# Ethernet.net
KiCad netlist of a schematic drawn in Altium Designer
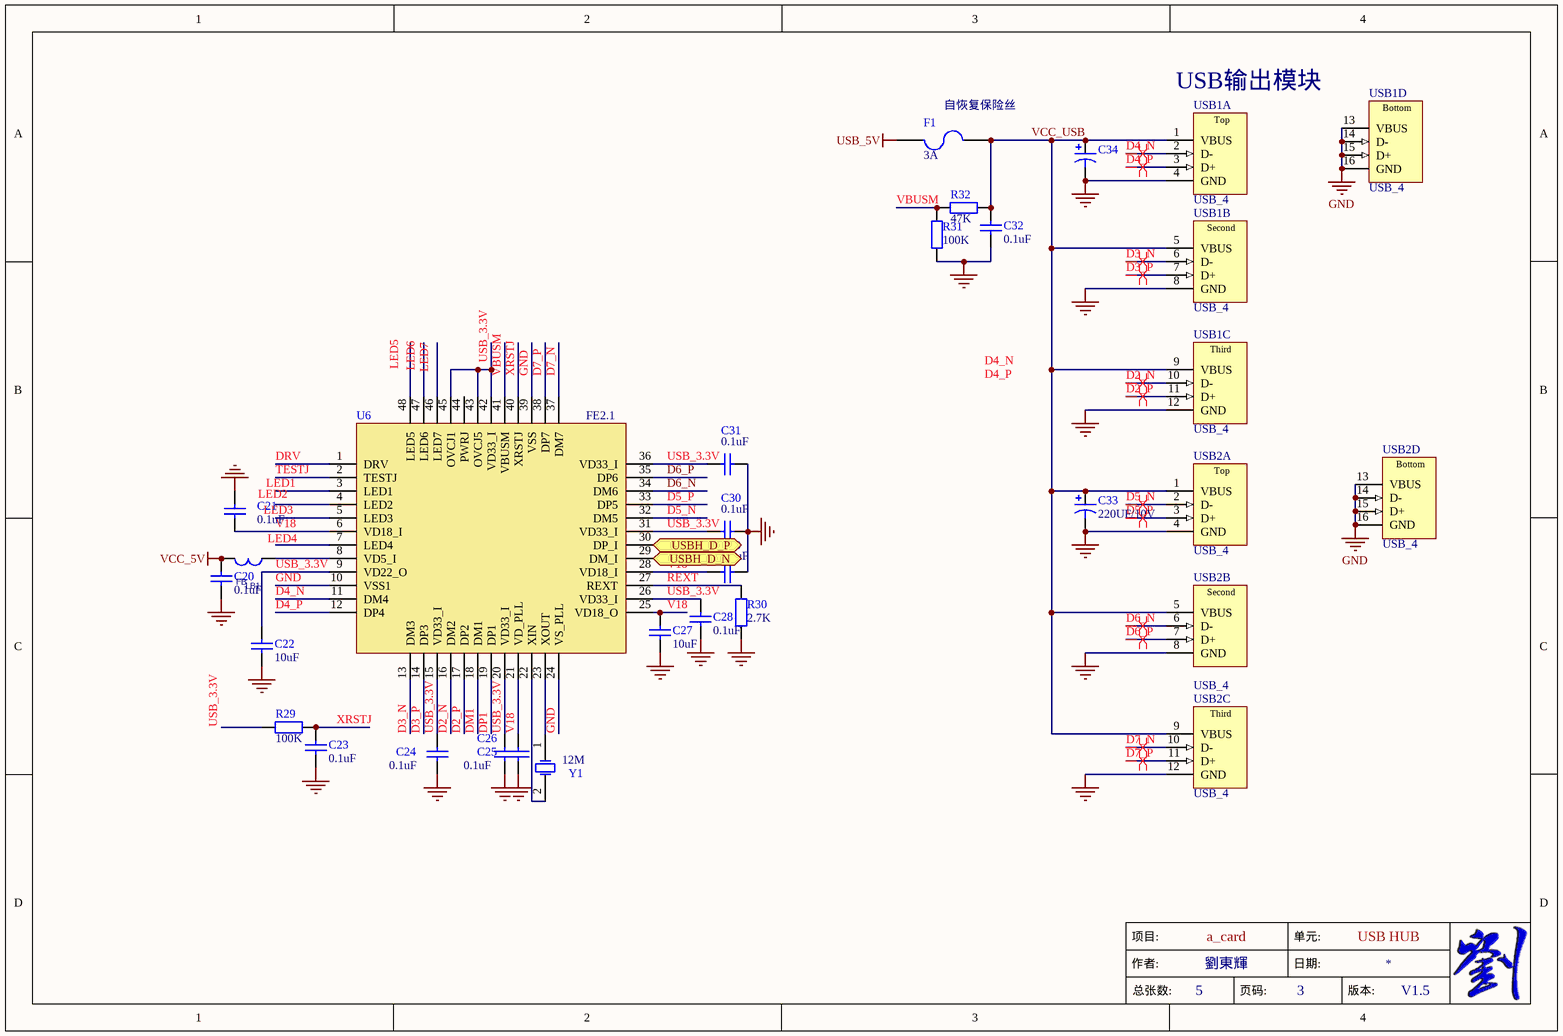
[diagram p0: Ethernet.SchDoc]

(export (version "E")
  (design (tool "Eeschema 10.0.6"))
  (components
    (comp (ref "C20")
      (value "0.1uF")
      (footprint "0805/2012 C3")
      (description "Capacitor")
      (fields (field (name "PUBLISHER") "*"))
      (libsource (lib "*") (part "Cap"))
    )
    (comp (ref "C21")
      (value "0.1uF")
      (footprint "0805/2012 C3")
      (description "Capacitor")
      (fields (field (name "PUBLISHER") "*"))
      (libsource (lib "*") (part "Cap"))
    )
    (comp (ref "C22")
      (value "10uF")
      (footprint "0805/2012 C3")
      (description "Capacitor")
      (fields (field (name "PUBLISHER") "*"))
      (libsource (lib "*") (part "Cap"))
    )
    (comp (ref "C23")
      (value "0.1uF")
      (footprint "0805/2012 C3")
      (description "Capacitor")
      (fields (field (name "PUBLISHER") "Altium Limited"))
      (libsource (lib "*") (part "Cap"))
    )
    (comp (ref "C24")
      (value "0.1uF")
      (footprint "0805/2012 C3")
      (description "Capacitor")
      (fields (field (name "PUBLISHER") "*"))
      (libsource (lib "*") (part "Cap"))
    )
    (comp (ref "C25")
      (value "0.1uF")
      (footprint "0805/2012 C3")
      (description "Capacitor")
      (fields (field (name "PUBLISHER") "Altium Limited"))
      (libsource (lib "*") (part "Cap"))
    )
    (comp (ref "C26")
      (value "0.1uF")
      (footprint "0805/2012 C3")
      (description "Capacitor")
      (fields (field (name "PUBLISHER") "Altium Limited"))
      (libsource (lib "*") (part "Cap"))
    )
    (comp (ref "C27")
      (value "10uF")
      (footprint "0805/2012 C3")
      (description "Capacitor")
      (fields (field (name "PUBLISHER") "*"))
      (libsource (lib "*") (part "Cap"))
    )
    (comp (ref "C28")
      (value "0.1uF")
      (footprint "0805/2012 C3")
      (description "Capacitor")
      (fields (field (name "PUBLISHER") "Altium Limited"))
      (libsource (lib "*") (part "Cap"))
    )
    (comp (ref "C29")
      (value "0.1uF")
      (footprint "0805/2012 C3")
      (description "Capacitor")
      (fields (field (name "PUBLISHER") "Altium Limited"))
      (libsource (lib "*") (part "Cap"))
    )
    (comp (ref "C30")
      (value "0.1uF")
      (footprint "0805/2012 C3")
      (description "Capacitor")
      (fields (field (name "PUBLISHER") "*"))
      (libsource (lib "*") (part "Cap"))
    )
    (comp (ref "C31")
      (value "0.1uF")
      (footprint "0805/2012 C3")
      (description "Capacitor")
      (fields (field (name "PUBLISHER") "Altium Limited"))
      (libsource (lib "*") (part "Cap"))
    )
    (comp (ref "C32")
      (value "0.1uF")
      (footprint "0805/2012 C3")
      (description "Capacitor")
      (fields (field (name "PUBLISHER") "Altium Limited"))
      (libsource (lib "*") (part "Cap"))
    )
    (comp (ref "C33")
      (value "220UF/10V")
      (footprint "2312_6023-20_SMT-TAJ-F")
      (description "Polarized Capacitor (Radial)")
      (fields (field (name "PUBLISHER") "Altium Limited"))
      (libsource (lib "*") (part "Cap Pol1"))
    )
    (comp (ref "C34")
      (value "220UF/10V")
      (footprint "2312_6023-20_SMT-TAJ-F")
      (description "Polarized Capacitor (Radial)")
      (fields (field (name "PUBLISHER") "*"))
      (libsource (lib "*") (part "Cap Pol1"))
    )
    (comp (ref "F1")
      (value "3A")
      (footprint "PPTC 1812/4532")
      (description "Fuse")
      (fields (field (name "PUBLISHER") "Altium Limited"))
      (libsource (lib "*") (part "Fuse 2"))
    )
    (comp (ref "LB1") (value "FB") (footprint "0805/2012 F3") (libsource (lib "*") (part "FB-0805")))
    (comp (ref "R29")
      (value "100K")
      (footprint "0805/2012 R3")
      (description "Resistor")
      (fields (field (name "PUBLISHER") "Altium Limited"))
      (libsource (lib "") (part "Res2_1"))
    )
    (comp (ref "R30")
      (value "2.7K")
      (footprint "0805/2012 R3")
      (description "Resistor")
      (fields (field (name "PUBLISHER") "*"))
      (libsource (lib "") (part "Res2_2"))
    )
    (comp (ref "R31")
      (value "100K")
      (footprint "0805/2012 R3")
      (description "Resistor")
      (fields (field (name "PUBLISHER") "Altium Limited"))
      (libsource (lib "") (part "Res2_1"))
    )
    (comp (ref "R32")
      (value "47K")
      (footprint "0805/2012 R3")
      (description "Resistor")
      (fields (field (name "PUBLISHER") "Altium Limited"))
      (libsource (lib "*") (part "Res2"))
    )
    (comp (ref "U6") (value "FE2.1") (footprint "LQFP-48L") (libsource (lib "*") (part "F2.1")))
    (comp (ref "USB1")
      (value "USB_4")
      (footprint "USB-3")
      (description "USB 1.1, Right Angle, Thru-Hole, A Type, Receptacle, 4x4x4x4 Position, Fourfold Stacked, Black")
      (fields (field (name "PUBLISHER") "Altium Limited"))
      (libsource (lib "USB.RJ45.SD.sim") (part "USB_4"))
    )
    (comp (ref "USB2")
      (value "USB_4")
      (footprint "USB-3")
      (description "USB 1.1, Right Angle, Thru-Hole, A Type, Receptacle, 4x4x4x4 Position, Fourfold Stacked, Black")
      (fields (field (name "PUBLISHER") "Altium Limited"))
      (libsource (lib "USB.RJ45.SD.sim") (part "USB_4"))
    )
    (comp (ref "Y1")
      (value "12M")
      (footprint "XTAL_CITIZEN_HCM49")
      (description "Crystal Oscillator")
      (fields (field (name "PUBLISHER") "*"))
      (libsource (lib "*") (part "XTAL"))
    )
  )
  (nets
    (net (code "1") (name "/D2_N") (class "Default")
      (node (ref "U6") (pin "16") (pinfunction "DM2_16") (pintype "passive"))
      (node (ref "USB1") (pin "10") (pinfunction "D-_10") (pintype "input"))
    )
    (net (code "2") (name "/D2_P") (class "Default")
      (node (ref "U6") (pin "17") (pinfunction "DP2_17") (pintype "passive"))
      (node (ref "USB1") (pin "11") (pinfunction "D+_11") (pintype "input"))
    )
    (net (code "3") (name "/D3_N") (class "Default")
      (node (ref "U6") (pin "13") (pinfunction "DM3_13") (pintype "passive"))
      (node (ref "USB1") (pin "6") (pinfunction "D-_6") (pintype "input"))
    )
    (net (code "4") (name "/D3_P") (class "Default")
      (node (ref "U6") (pin "14") (pinfunction "DP3_14") (pintype "passive"))
      (node (ref "USB1") (pin "7") (pinfunction "D+_7") (pintype "input"))
    )
    (net (code "5") (name "/D4_N") (class "Default")
      (node (ref "U6") (pin "11") (pinfunction "DM4_11") (pintype "passive"))
      (node (ref "USB1") (pin "2") (pinfunction "D-_2") (pintype "input"))
    )
    (net (code "6") (name "/D4_P") (class "Default")
      (node (ref "U6") (pin "12") (pinfunction "DP4_12") (pintype "passive"))
      (node (ref "USB1") (pin "3") (pinfunction "D+_3") (pintype "input"))
    )
    (net (code "7") (name "/D5_N") (class "Default")
      (node (ref "U6") (pin "32") (pinfunction "DM5_32") (pintype "passive"))
      (node (ref "USB2") (pin "2") (pinfunction "D-_2") (pintype "input"))
    )
    (net (code "8") (name "/D5_P") (class "Default")
      (node (ref "U6") (pin "33") (pinfunction "DP5_33") (pintype "passive"))
      (node (ref "USB2") (pin "3") (pinfunction "D+_3") (pintype "input"))
    )
    (net (code "9") (name "/D6_N") (class "Default")
      (node (ref "U6") (pin "34") (pinfunction "DM6_34") (pintype "passive"))
      (node (ref "USB2") (pin "6") (pinfunction "D-_6") (pintype "input"))
    )
    (net (code "10") (name "/D6_P") (class "Default")
      (node (ref "U6") (pin "35") (pinfunction "DP6_35") (pintype "passive"))
      (node (ref "USB2") (pin "7") (pinfunction "D+_7") (pintype "input"))
    )
    (net (code "11") (name "/D7_N") (class "Default")
      (node (ref "U6") (pin "37") (pinfunction "DM7_37") (pintype "passive"))
      (node (ref "USB2") (pin "10") (pinfunction "D-_10") (pintype "input"))
    )
    (net (code "12") (name "/D7_P") (class "Default")
      (node (ref "U6") (pin "38") (pinfunction "DP7_38") (pintype "passive"))
      (node (ref "USB2") (pin "11") (pinfunction "D+_11") (pintype "input"))
    )
    (net (code "13") (name "/DM1") (class "Default")
      (node (ref "U6") (pin "18") (pinfunction "DM1_18") (pintype "passive"))
    )
    (net (code "14") (name "/DP1") (class "Default")
      (node (ref "U6") (pin "19") (pinfunction "DP1_19") (pintype "passive"))
    )
    (net (code "15") (name "/DRV") (class "Default")
      (node (ref "U6") (pin "1") (pinfunction "DRV_1") (pintype "passive"))
    )
    (net (code "23") (name "/REXT") (class "Default")
      (node (ref "R30") (pin "2") (pinfunction "2_2") (pintype "passive"))
      (node (ref "U6") (pin "27") (pinfunction "REXT_27") (pintype "passive"))
    )
    (net (code "24") (name "/TESTJ") (class "Default")
      (node (ref "U6") (pin "2") (pinfunction "TESTJ_2") (pintype "passive"))
    )
    (net (code "25") (name "/USBH_D_N") (class "Default")
      (node (ref "U6") (pin "29") (pinfunction "DM_I_29") (pintype "passive"))
    )
    (net (code "26") (name "/USBH_D_P") (class "Default")
      (node (ref "U6") (pin "30") (pinfunction "DP_I_30") (pintype "passive"))
    )
    (net (code "27") (name "/USB_3.3V") (class "Default")
      (node (ref "C22") (pin "2") (pinfunction "2_2") (pintype "passive"))
      (node (ref "C24") (pin "2") (pinfunction "2_2") (pintype "passive"))
      (node (ref "C25") (pin "2") (pinfunction "2_2") (pintype "passive"))
      (node (ref "C28") (pin "2") (pinfunction "2_2") (pintype "passive"))
      (node (ref "C30") (pin "2") (pinfunction "2_2") (pintype "passive"))
      (node (ref "C31") (pin "2") (pinfunction "2_2") (pintype "passive"))
      (node (ref "R29") (pin "1") (pinfunction "1_1") (pintype "passive"))
      (node (ref "U6") (pin "15") (pinfunction "VD33_I_15") (pintype "passive"))
      (node (ref "U6") (pin "20") (pinfunction "VD33_I_20") (pintype "passive"))
      (node (ref "U6") (pin "26") (pinfunction "VD33_I_26") (pintype "passive"))
      (node (ref "U6") (pin "31") (pinfunction "VD33_I_31") (pintype "passive"))
      (node (ref "U6") (pin "36") (pinfunction "VD33_I_36") (pintype "passive"))
      (node (ref "U6") (pin "42") (pinfunction "VD33_I_42") (pintype "passive"))
      (node (ref "U6") (pin "43") (pinfunction "OVCJ5_43") (pintype "passive"))
      (node (ref "U6") (pin "45") (pinfunction "OVCJ1_45") (pintype "passive"))
      (node (ref "U6") (pin "9") (pinfunction "VD22_O_9") (pintype "passive"))
    )
    (net (code "28") (name "/V18") (class "Default")
      (node (ref "C21") (pin "2") (pinfunction "2_2") (pintype "passive"))
      (node (ref "C26") (pin "2") (pinfunction "2_2") (pintype "passive"))
      (node (ref "C27") (pin "2") (pinfunction "2_2") (pintype "passive"))
      (node (ref "C29") (pin "2") (pinfunction "2_2") (pintype "passive"))
      (node (ref "U6") (pin "21") (pinfunction "VD_PLL_21") (pintype "passive"))
      (node (ref "U6") (pin "25") (pinfunction "VD18_O_25") (pintype "passive"))
      (node (ref "U6") (pin "28") (pinfunction "VD18_I_28") (pintype "passive"))
      (node (ref "U6") (pin "6") (pinfunction "VD18_I_6") (pintype "passive"))
    )
    (net (code "29") (name "/VBUSM") (class "Default")
      (node (ref "R31") (pin "2") (pinfunction "2_2") (pintype "passive"))
      (node (ref "R32") (pin "2") (pinfunction "2_2") (pintype "passive"))
      (node (ref "U6") (pin "41") (pinfunction "VBUSM_41") (pintype "passive"))
    )
    (net (code "30") (name "/VCC_USB") (class "Default")
      (node (ref "C32") (pin "2") (pinfunction "2_2") (pintype "passive"))
      (node (ref "C33") (pin "1") (pinfunction "1_1") (pintype "passive"))
      (node (ref "C34") (pin "1") (pinfunction "1_1") (pintype "passive"))
      (node (ref "F1") (pin "1") (pinfunction "1_1") (pintype "passive"))
      (node (ref "R32") (pin "1") (pinfunction "1_1") (pintype "passive"))
      (node (ref "USB1") (pin "1") (pinfunction "VBUS_1") (pintype "power_in"))
      (node (ref "USB1") (pin "5") (pinfunction "VBUS_5") (pintype "power_in"))
      (node (ref "USB1") (pin "9") (pinfunction "VBUS_9") (pintype "power_in"))
      (node (ref "USB2") (pin "1") (pinfunction "VBUS_1") (pintype "power_in"))
      (node (ref "USB2") (pin "5") (pinfunction "VBUS_5") (pintype "power_in"))
      (node (ref "USB2") (pin "9") (pinfunction "VBUS_9") (pintype "power_in"))
    )
    (net (code "31") (name "/XRSTJ") (class "Default")
      (node (ref "C23") (pin "2") (pinfunction "2_2") (pintype "passive"))
      (node (ref "R29") (pin "2") (pinfunction "2_2") (pintype "passive"))
      (node (ref "U6") (pin "40") (pinfunction "XRSTJ_40") (pintype "passive"))
    )
    (net (code "32") (name "GND") (class "Default")
      (node (ref "C20") (pin "1") (pinfunction "1_1") (pintype "passive"))
      (node (ref "C21") (pin "1") (pinfunction "1_1") (pintype "passive"))
      (node (ref "C22") (pin "1") (pinfunction "1_1") (pintype "passive"))
      (node (ref "C23") (pin "1") (pinfunction "1_1") (pintype "passive"))
      (node (ref "C24") (pin "1") (pinfunction "1_1") (pintype "passive"))
      (node (ref "C25") (pin "1") (pinfunction "1_1") (pintype "passive"))
      (node (ref "C26") (pin "1") (pinfunction "1_1") (pintype "passive"))
      (node (ref "C27") (pin "1") (pinfunction "1_1") (pintype "passive"))
      (node (ref "C28") (pin "1") (pinfunction "1_1") (pintype "passive"))
      (node (ref "C29") (pin "1") (pinfunction "1_1") (pintype "passive"))
      (node (ref "C30") (pin "1") (pinfunction "1_1") (pintype "passive"))
      (node (ref "C31") (pin "1") (pinfunction "1_1") (pintype "passive"))
      (node (ref "C32") (pin "1") (pinfunction "1_1") (pintype "passive"))
      (node (ref "C33") (pin "2") (pinfunction "2_2") (pintype "passive"))
      (node (ref "C34") (pin "2") (pinfunction "2_2") (pintype "passive"))
      (node (ref "R30") (pin "1") (pinfunction "1_1") (pintype "passive"))
      (node (ref "R31") (pin "1") (pinfunction "1_1") (pintype "passive"))
      (node (ref "U6") (pin "10") (pinfunction "VSS1_10") (pintype "passive"))
      (node (ref "U6") (pin "24") (pinfunction "VS_PLL_24") (pintype "passive"))
      (node (ref "U6") (pin "39") (pinfunction "VSS_39") (pintype "passive"))
      (node (ref "USB1") (pin "12") (pinfunction "GND_12") (pintype "power_in"))
      (node (ref "USB1") (pin "13") (pinfunction "VBUS_13") (pintype "power_in"))
      (node (ref "USB1") (pin "14") (pinfunction "D-_14") (pintype "input"))
      (node (ref "USB1") (pin "15") (pinfunction "D+_15") (pintype "input"))
      (node (ref "USB1") (pin "16") (pinfunction "GND_16") (pintype "power_in"))
      (node (ref "USB1") (pin "4") (pinfunction "GND_4") (pintype "power_in"))
      (node (ref "USB1") (pin "8") (pinfunction "GND_8") (pintype "power_in"))
      (node (ref "USB2") (pin "12") (pinfunction "GND_12") (pintype "power_in"))
      (node (ref "USB2") (pin "13") (pinfunction "VBUS_13") (pintype "power_in"))
      (node (ref "USB2") (pin "14") (pinfunction "D-_14") (pintype "input"))
      (node (ref "USB2") (pin "15") (pinfunction "D+_15") (pintype "input"))
      (node (ref "USB2") (pin "16") (pinfunction "GND_16") (pintype "power_in"))
      (node (ref "USB2") (pin "4") (pinfunction "GND_4") (pintype "power_in"))
      (node (ref "USB2") (pin "8") (pinfunction "GND_8") (pintype "power_in"))
    )
    (net (code "33") (name "Net-(U6-VD5_I)") (class "Default")
      (node (ref "LB1") (pin "1") (pinfunction "1_1") (pintype "passive"))
      (node (ref "U6") (pin "8") (pinfunction "VD5_I_8") (pintype "passive"))
    )
    (net (code "34") (name "Net-(U6-XIN)") (class "Default")
      (node (ref "U6") (pin "22") (pinfunction "XIN_22") (pintype "passive"))
      (node (ref "Y1") (pin "2") (pinfunction "OSC2_2") (pintype "passive"))
    )
    (net (code "35") (name "Net-(U6-XOUT)") (class "Default")
      (node (ref "U6") (pin "23") (pinfunction "XOUT_23") (pintype "passive"))
      (node (ref "Y1") (pin "1") (pinfunction "OSC1_1") (pintype "passive"))
    )
    (net (code "36") (name "USB_5V") (class "Default")
      (node (ref "F1") (pin "2") (pinfunction "2_2") (pintype "passive"))
    )
    (net (code "37") (name "VCC_5V") (class "Default")
      (node (ref "C20") (pin "2") (pinfunction "2_2") (pintype "passive"))
      (node (ref "LB1") (pin "2") (pinfunction "2_2") (pintype "passive"))
    )
    (net (code "38") (name "unconnected-(U6-LED1-Pad3)") (class "Default")
      (node (ref "U6") (pin "3") (pinfunction "LED1_3") (pintype "passive"))
    )
    (net (code "39") (name "unconnected-(U6-LED2-Pad4)") (class "Default")
      (node (ref "U6") (pin "4") (pinfunction "LED2_4") (pintype "passive"))
    )
    (net (code "40") (name "unconnected-(U6-LED3-Pad5)") (class "Default")
      (node (ref "U6") (pin "5") (pinfunction "LED3_5") (pintype "passive"))
    )
    (net (code "41") (name "unconnected-(U6-LED4-Pad7)") (class "Default")
      (node (ref "U6") (pin "7") (pinfunction "LED4_7") (pintype "passive"))
    )
    (net (code "42") (name "unconnected-(U6-LED5-Pad48)") (class "Default")
      (node (ref "U6") (pin "48") (pinfunction "LED5_48") (pintype "passive"))
    )
    (net (code "43") (name "unconnected-(U6-LED6-Pad47)") (class "Default")
      (node (ref "U6") (pin "47") (pinfunction "LED6_47") (pintype "passive"))
    )
    (net (code "44") (name "unconnected-(U6-LED7-Pad46)") (class "Default")
      (node (ref "U6") (pin "46") (pinfunction "LED7_46") (pintype "passive"))
    )
    (net (code "45") (name "unconnected-(U6-PWRJ-Pad44)") (class "Default")
      (node (ref "U6") (pin "44") (pinfunction "PWRJ_44") (pintype "passive"))
    )
  )
)
